# TestFetTurnOffBattery.net
KiCad netlist of a schematic drawn in EAGLE
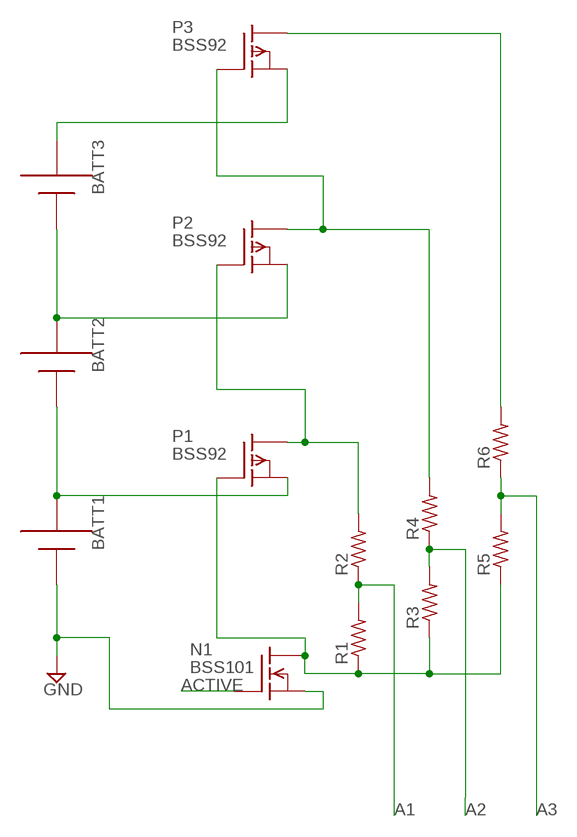
[diagram p0: schematic, sheet 1]

(export (version "E")
  (design (tool "Eeschema 10.0.6"))
  (components
    (comp (ref "BATT1")
      (value "AAA")
      (footprint "eagle-import:12BH412")
      (libsource (lib "eagle-import") (part "AAA"))
    )
    (comp (ref "BATT2")
      (value "AAA")
      (footprint "eagle-import:12BH412")
      (libsource (lib "eagle-import") (part "AAA"))
    )
    (comp (ref "BATT3")
      (value "AAA")
      (footprint "eagle-import:12BH412")
      (libsource (lib "eagle-import") (part "AAA"))
    )
    (comp (ref "N1")
      (value "BSS101")
      (footprint "eagle-import:TO92")
      (libsource (lib "eagle-import") (part "BSS101"))
    )
    (comp (ref "P1")
      (value "BSS92")
      (footprint "eagle-import:TO92")
      (libsource (lib "eagle-import") (part "BSS92"))
    )
    (comp (ref "P2")
      (value "BSS92")
      (footprint "eagle-import:TO92")
      (libsource (lib "eagle-import") (part "BSS92"))
    )
    (comp (ref "P3")
      (value "BSS92")
      (footprint "eagle-import:TO92")
      (libsource (lib "eagle-import") (part "BSS92"))
    )
    (comp (ref "R1")
      (value "R-US_R0603")
      (footprint "eagle-import:R0603")
      (libsource (lib "eagle-import") (part "R-US_R0603"))
    )
    (comp (ref "R2")
      (value "R-US_R0603")
      (footprint "eagle-import:R0603")
      (libsource (lib "eagle-import") (part "R-US_R0603"))
    )
    (comp (ref "R3")
      (value "R-US_R0603")
      (footprint "eagle-import:R0603")
      (libsource (lib "eagle-import") (part "R-US_R0603"))
    )
    (comp (ref "R4")
      (value "R-US_R0603")
      (footprint "eagle-import:R0603")
      (libsource (lib "eagle-import") (part "R-US_R0603"))
    )
    (comp (ref "R5")
      (value "R-US_R0603")
      (footprint "eagle-import:R0603")
      (libsource (lib "eagle-import") (part "R-US_R0603"))
    )
    (comp (ref "R6")
      (value "R-US_R0603")
      (footprint "eagle-import:R0603")
      (libsource (lib "eagle-import") (part "R-US_R0603"))
    )
  )
  (nets
    (net (code "1") (name "/A1") (class "Default")
      (node (ref "R1") (pin "2") (pinfunction "2_2") (pintype "passive"))
      (node (ref "R2") (pin "1") (pinfunction "1_1") (pintype "passive"))
    )
    (net (code "2") (name "/A2") (class "Default")
      (node (ref "R3") (pin "2") (pinfunction "2_2") (pintype "passive"))
      (node (ref "R4") (pin "1") (pinfunction "1_1") (pintype "passive"))
    )
    (net (code "3") (name "/A3") (class "Default")
      (node (ref "R5") (pin "2") (pinfunction "2_2") (pintype "passive"))
      (node (ref "R6") (pin "1") (pinfunction "1_1") (pintype "passive"))
    )
    (net (code "4") (name "/ACTIVE") (class "Default")
      (node (ref "N1") (pin "2") (pinfunction "G_2") (pintype "passive"))
    )
    (net (code "5") (name "GND") (class "Default")
      (node (ref "BATT1") (pin "+") (pinfunction "+_+") (pintype "bidirectional"))
      (node (ref "N1") (pin "1") (pinfunction "S_1") (pintype "passive"))
    )
    (net (code "6") (name "Net-(N1-D)") (class "Default")
      (node (ref "N1") (pin "3") (pinfunction "D_3") (pintype "passive"))
      (node (ref "P1") (pin "1") (pinfunction "G_1") (pintype "passive"))
      (node (ref "R1") (pin "1") (pinfunction "1_1") (pintype "passive"))
      (node (ref "R3") (pin "1") (pinfunction "1_1") (pintype "passive"))
      (node (ref "R5") (pin "1") (pinfunction "1_1") (pintype "passive"))
    )
    (net (code "7") (name "Net-(P1-D)") (class "Default")
      (node (ref "P1") (pin "2") (pinfunction "D_2") (pintype "passive"))
      (node (ref "P2") (pin "1") (pinfunction "G_1") (pintype "passive"))
      (node (ref "R2") (pin "2") (pinfunction "2_2") (pintype "passive"))
    )
    (net (code "8") (name "Net-(P1-S)") (class "Default")
      (node (ref "BATT1") (pin "-") (pinfunction "-_-") (pintype "bidirectional"))
      (node (ref "BATT2") (pin "+") (pinfunction "+_+") (pintype "bidirectional"))
      (node (ref "P1") (pin "3") (pinfunction "S_3") (pintype "passive"))
    )
    (net (code "9") (name "Net-(P2-D)") (class "Default")
      (node (ref "P2") (pin "2") (pinfunction "D_2") (pintype "passive"))
      (node (ref "P3") (pin "1") (pinfunction "G_1") (pintype "passive"))
      (node (ref "R4") (pin "2") (pinfunction "2_2") (pintype "passive"))
    )
    (net (code "10") (name "Net-(P2-S)") (class "Default")
      (node (ref "BATT2") (pin "-") (pinfunction "-_-") (pintype "bidirectional"))
      (node (ref "BATT3") (pin "+") (pinfunction "+_+") (pintype "bidirectional"))
      (node (ref "P2") (pin "3") (pinfunction "S_3") (pintype "passive"))
    )
    (net (code "11") (name "Net-(P3-D)") (class "Default")
      (node (ref "P3") (pin "2") (pinfunction "D_2") (pintype "passive"))
      (node (ref "R6") (pin "2") (pinfunction "2_2") (pintype "passive"))
    )
    (net (code "12") (name "Net-(P3-S)") (class "Default")
      (node (ref "BATT3") (pin "-") (pinfunction "-_-") (pintype "bidirectional"))
      (node (ref "P3") (pin "3") (pinfunction "S_3") (pintype "passive"))
    )
  )
)
